# shift_register_MOSFET.net
KiCad netlist of a schematic drawn in EAGLE
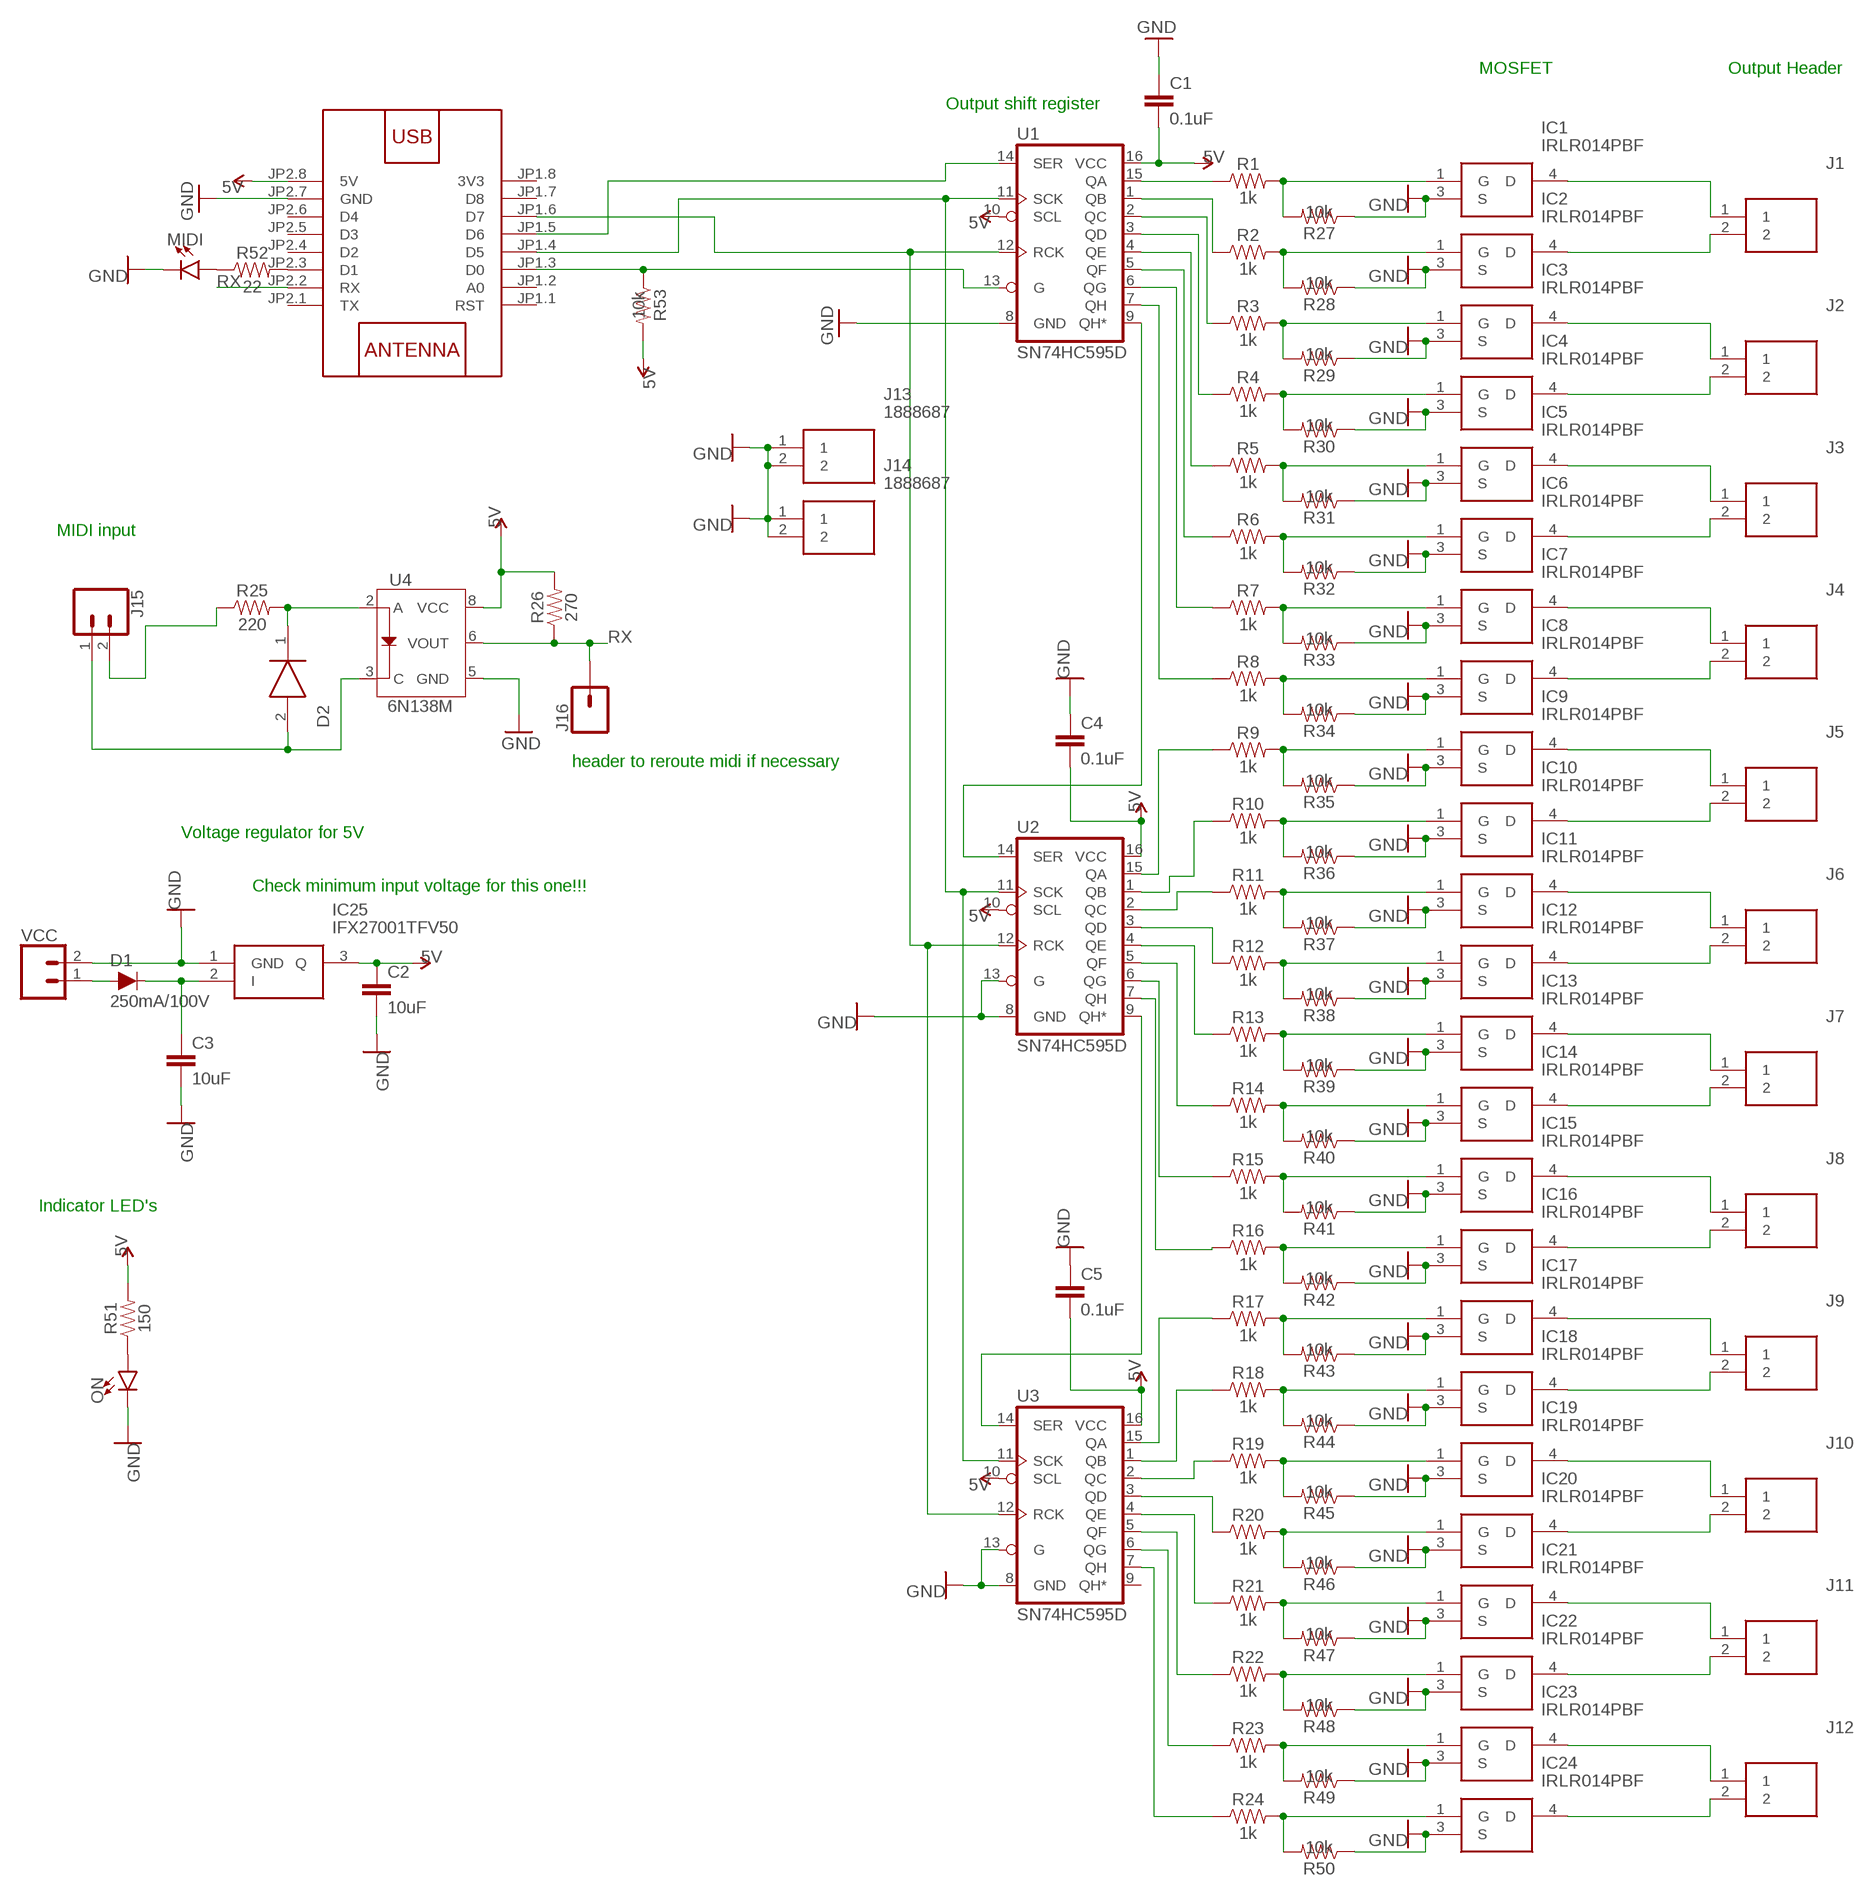
[diagram p0: schematic, sheet 1]

(export (version "E")
  (design (tool "Eeschema 10.0.6"))
  (components
    (comp (ref "C1")
      (value "0.1uF")
      (footprint "eagle-import:C0805")
      (libsource (lib "eagle-import") (part "C-EUC0805"))
    )
    (comp (ref "C2")
      (value "10uF")
      (footprint "eagle-import:C0805")
      (libsource (lib "eagle-import") (part "C-EUC0805"))
    )
    (comp (ref "C3")
      (value "10uF")
      (footprint "eagle-import:C0805")
      (libsource (lib "eagle-import") (part "C-EUC0805"))
    )
    (comp (ref "C4")
      (value "0.1uF")
      (footprint "eagle-import:C0805")
      (libsource (lib "eagle-import") (part "C-EUC0805"))
    )
    (comp (ref "C5")
      (value "0.1uF")
      (footprint "eagle-import:C0805")
      (libsource (lib "eagle-import") (part "C-EUC0805"))
    )
    (comp (ref "D1")
      (value "250mA/100V")
      (footprint "eagle-import:SOD-323")
      (libsource (lib "eagle-import") (part "DIODE-BAS16J"))
    )
    (comp (ref "D2")
      (value "1N914BWS")
      (footprint "eagle-import:SODFL2513X90N")
      (fields (field (name "MOUSER_PART_NUMBER") "512-1N914BWS") (field (name "RS_PART_NUMBER") "8051021P"))
      (libsource (lib "eagle-import") (part "1N914BWS"))
    )
    (comp (ref "IC1")
      (value "IRLR014PBF")
      (footprint "eagle-import:TO228P990X238-3N")
      (fields (field (name "MOUSER_PART_NUMBER") "844-IRLR014PBF") (field (name "RS_PART_NUMBER") "1780908"))
      (libsource (lib "eagle-import") (part "IRLR014PBF"))
    )
    (comp (ref "IC2")
      (value "IRLR014PBF")
      (footprint "eagle-import:TO228P990X238-3N")
      (fields (field (name "MOUSER_PART_NUMBER") "844-IRLR014PBF") (field (name "RS_PART_NUMBER") "1780908"))
      (libsource (lib "eagle-import") (part "IRLR014PBF"))
    )
    (comp (ref "IC3")
      (value "IRLR014PBF")
      (footprint "eagle-import:TO228P990X238-3N")
      (fields (field (name "MOUSER_PART_NUMBER") "844-IRLR014PBF") (field (name "RS_PART_NUMBER") "1780908"))
      (libsource (lib "eagle-import") (part "IRLR014PBF"))
    )
    (comp (ref "IC4")
      (value "IRLR014PBF")
      (footprint "eagle-import:TO228P990X238-3N")
      (fields (field (name "MOUSER_PART_NUMBER") "844-IRLR014PBF") (field (name "RS_PART_NUMBER") "1780908"))
      (libsource (lib "eagle-import") (part "IRLR014PBF"))
    )
    (comp (ref "IC5")
      (value "IRLR014PBF")
      (footprint "eagle-import:TO228P990X238-3N")
      (fields (field (name "MOUSER_PART_NUMBER") "844-IRLR014PBF") (field (name "RS_PART_NUMBER") "1780908"))
      (libsource (lib "eagle-import") (part "IRLR014PBF"))
    )
    (comp (ref "IC6")
      (value "IRLR014PBF")
      (footprint "eagle-import:TO228P990X238-3N")
      (fields (field (name "MOUSER_PART_NUMBER") "844-IRLR014PBF") (field (name "RS_PART_NUMBER") "1780908"))
      (libsource (lib "eagle-import") (part "IRLR014PBF"))
    )
    (comp (ref "IC7")
      (value "IRLR014PBF")
      (footprint "eagle-import:TO228P990X238-3N")
      (fields (field (name "MOUSER_PART_NUMBER") "844-IRLR014PBF") (field (name "RS_PART_NUMBER") "1780908"))
      (libsource (lib "eagle-import") (part "IRLR014PBF"))
    )
    (comp (ref "IC8")
      (value "IRLR014PBF")
      (footprint "eagle-import:TO228P990X238-3N")
      (fields (field (name "MOUSER_PART_NUMBER") "844-IRLR014PBF") (field (name "RS_PART_NUMBER") "1780908"))
      (libsource (lib "eagle-import") (part "IRLR014PBF"))
    )
    (comp (ref "IC9")
      (value "IRLR014PBF")
      (footprint "eagle-import:TO228P990X238-3N")
      (fields (field (name "MOUSER_PART_NUMBER") "844-IRLR014PBF") (field (name "RS_PART_NUMBER") "1780908"))
      (libsource (lib "eagle-import") (part "IRLR014PBF"))
    )
    (comp (ref "IC10")
      (value "IRLR014PBF")
      (footprint "eagle-import:TO228P990X238-3N")
      (fields (field (name "MOUSER_PART_NUMBER") "844-IRLR014PBF") (field (name "RS_PART_NUMBER") "1780908"))
      (libsource (lib "eagle-import") (part "IRLR014PBF"))
    )
    (comp (ref "IC11")
      (value "IRLR014PBF")
      (footprint "eagle-import:TO228P990X238-3N")
      (fields (field (name "MOUSER_PART_NUMBER") "844-IRLR014PBF") (field (name "RS_PART_NUMBER") "1780908"))
      (libsource (lib "eagle-import") (part "IRLR014PBF"))
    )
    (comp (ref "IC12")
      (value "IRLR014PBF")
      (footprint "eagle-import:TO228P990X238-3N")
      (fields (field (name "MOUSER_PART_NUMBER") "844-IRLR014PBF") (field (name "RS_PART_NUMBER") "1780908"))
      (libsource (lib "eagle-import") (part "IRLR014PBF"))
    )
    (comp (ref "IC13")
      (value "IRLR014PBF")
      (footprint "eagle-import:TO228P990X238-3N")
      (fields (field (name "MOUSER_PART_NUMBER") "844-IRLR014PBF") (field (name "RS_PART_NUMBER") "1780908"))
      (libsource (lib "eagle-import") (part "IRLR014PBF"))
    )
    (comp (ref "IC14")
      (value "IRLR014PBF")
      (footprint "eagle-import:TO228P990X238-3N")
      (fields (field (name "MOUSER_PART_NUMBER") "844-IRLR014PBF") (field (name "RS_PART_NUMBER") "1780908"))
      (libsource (lib "eagle-import") (part "IRLR014PBF"))
    )
    (comp (ref "IC15")
      (value "IRLR014PBF")
      (footprint "eagle-import:TO228P990X238-3N")
      (fields (field (name "MOUSER_PART_NUMBER") "844-IRLR014PBF") (field (name "RS_PART_NUMBER") "1780908"))
      (libsource (lib "eagle-import") (part "IRLR014PBF"))
    )
    (comp (ref "IC16")
      (value "IRLR014PBF")
      (footprint "eagle-import:TO228P990X238-3N")
      (fields (field (name "MOUSER_PART_NUMBER") "844-IRLR014PBF") (field (name "RS_PART_NUMBER") "1780908"))
      (libsource (lib "eagle-import") (part "IRLR014PBF"))
    )
    (comp (ref "IC17")
      (value "IRLR014PBF")
      (footprint "eagle-import:TO228P990X238-3N")
      (fields (field (name "MOUSER_PART_NUMBER") "844-IRLR014PBF") (field (name "RS_PART_NUMBER") "1780908"))
      (libsource (lib "eagle-import") (part "IRLR014PBF"))
    )
    (comp (ref "IC18")
      (value "IRLR014PBF")
      (footprint "eagle-import:TO228P990X238-3N")
      (fields (field (name "MOUSER_PART_NUMBER") "844-IRLR014PBF") (field (name "RS_PART_NUMBER") "1780908"))
      (libsource (lib "eagle-import") (part "IRLR014PBF"))
    )
    (comp (ref "IC19")
      (value "IRLR014PBF")
      (footprint "eagle-import:TO228P990X238-3N")
      (fields (field (name "MOUSER_PART_NUMBER") "844-IRLR014PBF") (field (name "RS_PART_NUMBER") "1780908"))
      (libsource (lib "eagle-import") (part "IRLR014PBF"))
    )
    (comp (ref "IC20")
      (value "IRLR014PBF")
      (footprint "eagle-import:TO228P990X238-3N")
      (fields (field (name "MOUSER_PART_NUMBER") "844-IRLR014PBF") (field (name "RS_PART_NUMBER") "1780908"))
      (libsource (lib "eagle-import") (part "IRLR014PBF"))
    )
    (comp (ref "IC21")
      (value "IRLR014PBF")
      (footprint "eagle-import:TO228P990X238-3N")
      (fields (field (name "MOUSER_PART_NUMBER") "844-IRLR014PBF") (field (name "RS_PART_NUMBER") "1780908"))
      (libsource (lib "eagle-import") (part "IRLR014PBF"))
    )
    (comp (ref "IC22")
      (value "IRLR014PBF")
      (footprint "eagle-import:TO228P990X238-3N")
      (fields (field (name "MOUSER_PART_NUMBER") "844-IRLR014PBF") (field (name "RS_PART_NUMBER") "1780908"))
      (libsource (lib "eagle-import") (part "IRLR014PBF"))
    )
    (comp (ref "IC23")
      (value "IRLR014PBF")
      (footprint "eagle-import:TO228P990X238-3N")
      (fields (field (name "MOUSER_PART_NUMBER") "844-IRLR014PBF") (field (name "RS_PART_NUMBER") "1780908"))
      (libsource (lib "eagle-import") (part "IRLR014PBF"))
    )
    (comp (ref "IC24")
      (value "IRLR014PBF")
      (footprint "eagle-import:TO228P990X238-3N")
      (fields (field (name "MOUSER_PART_NUMBER") "844-IRLR014PBF") (field (name "RS_PART_NUMBER") "1780908"))
      (libsource (lib "eagle-import") (part "IRLR014PBF"))
    )
    (comp (ref "IC25")
      (value "IFX27001TFV50")
      (footprint "eagle-import:PG-TO252-3-11")
      (fields (field (name "RS_PART_NUMBER") "1459664"))
      (libsource (lib "eagle-import") (part "IFX27001TFV50"))
    )
    (comp (ref "J1")
      (value "1888687")
      (footprint "eagle-import:SHDR2W90P0X508_1X2_1016X950X15")
      (fields (field (name "MOUSER_PART_NUMBER") "651-1888687") (field (name "RS_PART_NUMBER") "2509972333"))
      (libsource (lib "eagle-import") (part "1888687"))
    )
    (comp (ref "J2")
      (value "1888687")
      (footprint "eagle-import:SHDR2W90P0X508_1X2_1016X950X15")
      (fields (field (name "MOUSER_PART_NUMBER") "651-1888687") (field (name "RS_PART_NUMBER") "2509972333"))
      (libsource (lib "eagle-import") (part "1888687"))
    )
    (comp (ref "J3")
      (value "1888687")
      (footprint "eagle-import:SHDR2W90P0X508_1X2_1016X950X15")
      (fields (field (name "MOUSER_PART_NUMBER") "651-1888687") (field (name "RS_PART_NUMBER") "2509972333"))
      (libsource (lib "eagle-import") (part "1888687"))
    )
    (comp (ref "J4")
      (value "1888687")
      (footprint "eagle-import:SHDR2W90P0X508_1X2_1016X950X15")
      (fields (field (name "MOUSER_PART_NUMBER") "651-1888687") (field (name "RS_PART_NUMBER") "2509972333"))
      (libsource (lib "eagle-import") (part "1888687"))
    )
    (comp (ref "J5")
      (value "1888687")
      (footprint "eagle-import:SHDR2W90P0X508_1X2_1016X950X15")
      (fields (field (name "MOUSER_PART_NUMBER") "651-1888687") (field (name "RS_PART_NUMBER") "2509972333"))
      (libsource (lib "eagle-import") (part "1888687"))
    )
    (comp (ref "J6")
      (value "1888687")
      (footprint "eagle-import:SHDR2W90P0X508_1X2_1016X950X15")
      (fields (field (name "MOUSER_PART_NUMBER") "651-1888687") (field (name "RS_PART_NUMBER") "2509972333"))
      (libsource (lib "eagle-import") (part "1888687"))
    )
    (comp (ref "J7")
      (value "1888687")
      (footprint "eagle-import:SHDR2W90P0X508_1X2_1016X950X15")
      (fields (field (name "MOUSER_PART_NUMBER") "651-1888687") (field (name "RS_PART_NUMBER") "2509972333"))
      (libsource (lib "eagle-import") (part "1888687"))
    )
    (comp (ref "J8")
      (value "1888687")
      (footprint "eagle-import:SHDR2W90P0X508_1X2_1016X950X15")
      (fields (field (name "MOUSER_PART_NUMBER") "651-1888687") (field (name "RS_PART_NUMBER") "2509972333"))
      (libsource (lib "eagle-import") (part "1888687"))
    )
    (comp (ref "J9")
      (value "1888687")
      (footprint "eagle-import:SHDR2W90P0X508_1X2_1016X950X15")
      (fields (field (name "MOUSER_PART_NUMBER") "651-1888687") (field (name "RS_PART_NUMBER") "2509972333"))
      (libsource (lib "eagle-import") (part "1888687"))
    )
    (comp (ref "J10")
      (value "1888687")
      (footprint "eagle-import:SHDR2W90P0X508_1X2_1016X950X15")
      (fields (field (name "MOUSER_PART_NUMBER") "651-1888687") (field (name "RS_PART_NUMBER") "2509972333"))
      (libsource (lib "eagle-import") (part "1888687"))
    )
    (comp (ref "J11")
      (value "1888687")
      (footprint "eagle-import:SHDR2W90P0X508_1X2_1016X950X15")
      (fields (field (name "MOUSER_PART_NUMBER") "651-1888687") (field (name "RS_PART_NUMBER") "2509972333"))
      (libsource (lib "eagle-import") (part "1888687"))
    )
    (comp (ref "J12")
      (value "1888687")
      (footprint "eagle-import:SHDR2W90P0X508_1X2_1016X950X15")
      (fields (field (name "MOUSER_PART_NUMBER") "651-1888687") (field (name "RS_PART_NUMBER") "2509972333"))
      (libsource (lib "eagle-import") (part "1888687"))
    )
    (comp (ref "J13")
      (value "1888687")
      (footprint "eagle-import:SHDR2W90P0X508_1X2_1016X950X15")
      (fields (field (name "MOUSER_PART_NUMBER") "651-1888687") (field (name "RS_PART_NUMBER") "2509972333"))
      (libsource (lib "eagle-import") (part "1888687"))
    )
    (comp (ref "J14")
      (value "1888687")
      (footprint "eagle-import:SHDR2W90P0X508_1X2_1016X950X15")
      (fields (field (name "MOUSER_PART_NUMBER") "651-1888687") (field (name "RS_PART_NUMBER") "2509972333"))
      (libsource (lib "eagle-import") (part "1888687"))
    )
    (comp (ref "J15")
      (value "CONN_02")
      (footprint "eagle-import:1X02")
      (libsource (lib "eagle-import") (part "CONN_02"))
    )
    (comp (ref "J16")
      (value "CONN_01")
      (footprint "eagle-import:1X01")
      (libsource (lib "eagle-import") (part "CONN_01"))
    )
    (comp (ref "MIDI")
      (value "LED3MM")
      (footprint "eagle-import:LED_3MM")
      (libsource (lib "eagle-import") (part "LED3MM"))
    )
    (comp (ref "ON")
      (value "LED3MM")
      (footprint "eagle-import:LED_3MM")
      (libsource (lib "eagle-import") (part "LED3MM"))
    )
    (comp (ref "R1")
      (value "1k")
      (footprint "eagle-import:0805")
      (libsource (lib "eagle-import") (part "RESISTOR0805"))
    )
    (comp (ref "R2")
      (value "1k")
      (footprint "eagle-import:0805")
      (libsource (lib "eagle-import") (part "RESISTOR0805"))
    )
    (comp (ref "R3")
      (value "1k")
      (footprint "eagle-import:0805")
      (libsource (lib "eagle-import") (part "RESISTOR0805"))
    )
    (comp (ref "R4")
      (value "1k")
      (footprint "eagle-import:0805")
      (libsource (lib "eagle-import") (part "RESISTOR0805"))
    )
    (comp (ref "R5")
      (value "1k")
      (footprint "eagle-import:0805")
      (libsource (lib "eagle-import") (part "RESISTOR0805"))
    )
    (comp (ref "R6")
      (value "1k")
      (footprint "eagle-import:0805")
      (libsource (lib "eagle-import") (part "RESISTOR0805"))
    )
    (comp (ref "R7")
      (value "1k")
      (footprint "eagle-import:0805")
      (libsource (lib "eagle-import") (part "RESISTOR0805"))
    )
    (comp (ref "R8")
      (value "1k")
      (footprint "eagle-import:0805")
      (libsource (lib "eagle-import") (part "RESISTOR0805"))
    )
    (comp (ref "R9")
      (value "1k")
      (footprint "eagle-import:0805")
      (libsource (lib "eagle-import") (part "RESISTOR0805"))
    )
    (comp (ref "R10")
      (value "1k")
      (footprint "eagle-import:0805")
      (libsource (lib "eagle-import") (part "RESISTOR0805"))
    )
    (comp (ref "R11")
      (value "1k")
      (footprint "eagle-import:0805")
      (libsource (lib "eagle-import") (part "RESISTOR0805"))
    )
    (comp (ref "R12")
      (value "1k")
      (footprint "eagle-import:0805")
      (libsource (lib "eagle-import") (part "RESISTOR0805"))
    )
    (comp (ref "R13")
      (value "1k")
      (footprint "eagle-import:0805")
      (libsource (lib "eagle-import") (part "RESISTOR0805"))
    )
    (comp (ref "R14")
      (value "1k")
      (footprint "eagle-import:0805")
      (libsource (lib "eagle-import") (part "RESISTOR0805"))
    )
    (comp (ref "R15")
      (value "1k")
      (footprint "eagle-import:0805")
      (libsource (lib "eagle-import") (part "RESISTOR0805"))
    )
    (comp (ref "R16")
      (value "1k")
      (footprint "eagle-import:0805")
      (libsource (lib "eagle-import") (part "RESISTOR0805"))
    )
    (comp (ref "R17")
      (value "1k")
      (footprint "eagle-import:0805")
      (libsource (lib "eagle-import") (part "RESISTOR0805"))
    )
    (comp (ref "R18")
      (value "1k")
      (footprint "eagle-import:0805")
      (libsource (lib "eagle-import") (part "RESISTOR0805"))
    )
    (comp (ref "R19")
      (value "1k")
      (footprint "eagle-import:0805")
      (libsource (lib "eagle-import") (part "RESISTOR0805"))
    )
    (comp (ref "R20")
      (value "1k")
      (footprint "eagle-import:0805")
      (libsource (lib "eagle-import") (part "RESISTOR0805"))
    )
    (comp (ref "R21")
      (value "1k")
      (footprint "eagle-import:0805")
      (libsource (lib "eagle-import") (part "RESISTOR0805"))
    )
    (comp (ref "R22")
      (value "1k")
      (footprint "eagle-import:0805")
      (libsource (lib "eagle-import") (part "RESISTOR0805"))
    )
    (comp (ref "R23")
      (value "1k")
      (footprint "eagle-import:0805")
      (libsource (lib "eagle-import") (part "RESISTOR0805"))
    )
    (comp (ref "R24")
      (value "1k")
      (footprint "eagle-import:0805")
      (libsource (lib "eagle-import") (part "RESISTOR0805"))
    )
    (comp (ref "R25")
      (value "220")
      (footprint "eagle-import:0805")
      (libsource (lib "eagle-import") (part "RESISTOR0805"))
    )
    (comp (ref "R26")
      (value "270")
      (footprint "eagle-import:0805")
      (libsource (lib "eagle-import") (part "RESISTOR0805"))
    )
    (comp (ref "R27")
      (value "10k")
      (footprint "eagle-import:0805")
      (libsource (lib "eagle-import") (part "RESISTOR0805"))
    )
    (comp (ref "R28")
      (value "10k")
      (footprint "eagle-import:0805")
      (libsource (lib "eagle-import") (part "RESISTOR0805"))
    )
    (comp (ref "R29")
      (value "10k")
      (footprint "eagle-import:0805")
      (libsource (lib "eagle-import") (part "RESISTOR0805"))
    )
    (comp (ref "R30")
      (value "10k")
      (footprint "eagle-import:0805")
      (libsource (lib "eagle-import") (part "RESISTOR0805"))
    )
    (comp (ref "R31")
      (value "10k")
      (footprint "eagle-import:0805")
      (libsource (lib "eagle-import") (part "RESISTOR0805"))
    )
    (comp (ref "R32")
      (value "10k")
      (footprint "eagle-import:0805")
      (libsource (lib "eagle-import") (part "RESISTOR0805"))
    )
    (comp (ref "R33")
      (value "10k")
      (footprint "eagle-import:0805")
      (libsource (lib "eagle-import") (part "RESISTOR0805"))
    )
    (comp (ref "R34")
      (value "10k")
      (footprint "eagle-import:0805")
      (libsource (lib "eagle-import") (part "RESISTOR0805"))
    )
    (comp (ref "R35")
      (value "10k")
      (footprint "eagle-import:0805")
      (libsource (lib "eagle-import") (part "RESISTOR0805"))
    )
    (comp (ref "R36")
      (value "10k")
      (footprint "eagle-import:0805")
      (libsource (lib "eagle-import") (part "RESISTOR0805"))
    )
    (comp (ref "R37")
      (value "10k")
      (footprint "eagle-import:0805")
      (libsource (lib "eagle-import") (part "RESISTOR0805"))
    )
    (comp (ref "R38")
      (value "10k")
      (footprint "eagle-import:0805")
      (libsource (lib "eagle-import") (part "RESISTOR0805"))
    )
    (comp (ref "R39")
      (value "10k")
      (footprint "eagle-import:0805")
      (libsource (lib "eagle-import") (part "RESISTOR0805"))
    )
    (comp (ref "R40")
      (value "10k")
      (footprint "eagle-import:0805")
      (libsource (lib "eagle-import") (part "RESISTOR0805"))
    )
    (comp (ref "R41")
      (value "10k")
      (footprint "eagle-import:0805")
      (libsource (lib "eagle-import") (part "RESISTOR0805"))
    )
    (comp (ref "R42")
      (value "10k")
      (footprint "eagle-import:0805")
      (libsource (lib "eagle-import") (part "RESISTOR0805"))
    )
    (comp (ref "R43")
      (value "10k")
      (footprint "eagle-import:0805")
      (libsource (lib "eagle-import") (part "RESISTOR0805"))
    )
    (comp (ref "R44")
      (value "10k")
      (footprint "eagle-import:0805")
      (libsource (lib "eagle-import") (part "RESISTOR0805"))
    )
    (comp (ref "R45")
      (value "10k")
      (footprint "eagle-import:0805")
      (libsource (lib "eagle-import") (part "RESISTOR0805"))
    )
    (comp (ref "R46")
      (value "10k")
      (footprint "eagle-import:0805")
      (libsource (lib "eagle-import") (part "RESISTOR0805"))
    )
    (comp (ref "R47")
      (value "10k")
      (footprint "eagle-import:0805")
      (libsource (lib "eagle-import") (part "RESISTOR0805"))
    )
    (comp (ref "R48")
      (value "10k")
      (footprint "eagle-import:0805")
      (libsource (lib "eagle-import") (part "RESISTOR0805"))
    )
    (comp (ref "R49")
      (value "10k")
      (footprint "eagle-import:0805")
      (libsource (lib "eagle-import") (part "RESISTOR0805"))
    )
    (comp (ref "R50")
      (value "10k")
      (footprint "eagle-import:0805")
      (libsource (lib "eagle-import") (part "RESISTOR0805"))
    )
    (comp (ref "R51")
      (value "150")
      (footprint "eagle-import:0805")
      (libsource (lib "eagle-import") (part "RESISTOR0805"))
    )
    (comp (ref "R52")
      (value "22")
      (footprint "eagle-import:0805")
      (libsource (lib "eagle-import") (part "RESISTOR0805"))
    )
    (comp (ref "R53")
      (value "10k")
      (footprint "eagle-import:0805")
      (libsource (lib "eagle-import") (part "RESISTOR0805"))
    )
    (comp (ref "U$1")
      (value "WEMOS-D1-MINI")
      (footprint "eagle-import:WEMOS-D1-MINI")
      (libsource (lib "eagle-import") (part "WEMOS-D1-MINI"))
    )
    (comp (ref "U1")
      (value "SN74HC595D")
      (footprint "eagle-import:SO16")
      (libsource (lib "eagle-import") (part "74595DHC"))
    )
    (comp (ref "U2")
      (value "SN74HC595D")
      (footprint "eagle-import:SO16")
      (libsource (lib "eagle-import") (part "74595DHC"))
    )
    (comp (ref "U3")
      (value "SN74HC595D")
      (footprint "eagle-import:SO16")
      (libsource (lib "eagle-import") (part "74595DHC"))
    )
    (comp (ref "U4")
      (value "6N138M")
      (footprint "eagle-import:8-SMD")
      (libsource (lib "eagle-import") (part "OPTO_DARL_6N138S"))
    )
    (comp (ref "VCC")
      (value "CONN_02")
      (footprint "eagle-import:1X02")
      (libsource (lib "eagle-import") (part "CONN_02"))
    )
  )
  (nets
    (net (code "1") (name "/3V3") (class "Default")
      (node (ref "U$1") (pin "JP1.8") (pinfunction "3V3_JP1.8") (pintype "power_in"))
    )
    (net (code "2") (name "/RX") (class "Default")
      (node (ref "J16") (pin "1") (pinfunction "1_1") (pintype "passive"))
      (node (ref "R26") (pin "1") (pinfunction "1_1") (pintype "passive"))
      (node (ref "U$1") (pin "JP2.2") (pinfunction "RX_JP2.2") (pintype "bidirectional"))
      (node (ref "U4") (pin "6") (pinfunction "VOUT_6") (pintype "bidirectional"))
    )
    (net (code "3") (name "5V") (class "Default")
      (node (ref "C1") (pin "2") (pinfunction "2_2") (pintype "passive"))
      (node (ref "C2") (pin "1") (pinfunction "1_1") (pintype "passive"))
      (node (ref "C4") (pin "2") (pinfunction "2_2") (pintype "passive"))
      (node (ref "C5") (pin "2") (pinfunction "2_2") (pintype "passive"))
      (node (ref "IC25") (pin "3") (pinfunction "Q_3") (pintype "bidirectional"))
      (node (ref "R26") (pin "2") (pinfunction "2_2") (pintype "passive"))
      (node (ref "R51") (pin "2") (pinfunction "2_2") (pintype "passive"))
      (node (ref "R53") (pin "2") (pinfunction "2_2") (pintype "passive"))
      (node (ref "U$1") (pin "JP2.8") (pinfunction "5V_JP2.8") (pintype "power_in"))
      (node (ref "U1") (pin "10") (pinfunction "SCL_10") (pintype "input"))
      (node (ref "U1") (pin "16") (pinfunction "VCC_16") (pintype "power_in"))
      (node (ref "U2") (pin "10") (pinfunction "SCL_10") (pintype "input"))
      (node (ref "U2") (pin "16") (pinfunction "VCC_16") (pintype "power_in"))
      (node (ref "U3") (pin "10") (pinfunction "SCL_10") (pintype "input"))
      (node (ref "U3") (pin "16") (pinfunction "VCC_16") (pintype "power_in"))
      (node (ref "U4") (pin "8") (pinfunction "VCC_8") (pintype "bidirectional"))
    )
    (net (code "4") (name "GND") (class "Default")
      (node (ref "C1") (pin "1") (pinfunction "1_1") (pintype "passive"))
      (node (ref "C2") (pin "2") (pinfunction "2_2") (pintype "passive"))
      (node (ref "C3") (pin "2") (pinfunction "2_2") (pintype "passive"))
      (node (ref "C4") (pin "1") (pinfunction "1_1") (pintype "passive"))
      (node (ref "C5") (pin "1") (pinfunction "1_1") (pintype "passive"))
      (node (ref "IC1") (pin "3") (pinfunction "S_3") (pintype "bidirectional"))
      (node (ref "IC10") (pin "3") (pinfunction "S_3") (pintype "bidirectional"))
      (node (ref "IC11") (pin "3") (pinfunction "S_3") (pintype "bidirectional"))
      (node (ref "IC12") (pin "3") (pinfunction "S_3") (pintype "bidirectional"))
      (node (ref "IC13") (pin "3") (pinfunction "S_3") (pintype "bidirectional"))
      (node (ref "IC14") (pin "3") (pinfunction "S_3") (pintype "bidirectional"))
      (node (ref "IC15") (pin "3") (pinfunction "S_3") (pintype "bidirectional"))
      (node (ref "IC16") (pin "3") (pinfunction "S_3") (pintype "bidirectional"))
      (node (ref "IC17") (pin "3") (pinfunction "S_3") (pintype "bidirectional"))
      (node (ref "IC18") (pin "3") (pinfunction "S_3") (pintype "bidirectional"))
      (node (ref "IC19") (pin "3") (pinfunction "S_3") (pintype "bidirectional"))
      (node (ref "IC2") (pin "3") (pinfunction "S_3") (pintype "bidirectional"))
      (node (ref "IC20") (pin "3") (pinfunction "S_3") (pintype "bidirectional"))
      (node (ref "IC21") (pin "3") (pinfunction "S_3") (pintype "bidirectional"))
      (node (ref "IC22") (pin "3") (pinfunction "S_3") (pintype "bidirectional"))
      (node (ref "IC23") (pin "3") (pinfunction "S_3") (pintype "bidirectional"))
      (node (ref "IC24") (pin "3") (pinfunction "S_3") (pintype "bidirectional"))
      (node (ref "IC25") (pin "1") (pinfunction "GND_1") (pintype "bidirectional"))
      (node (ref "IC3") (pin "3") (pinfunction "S_3") (pintype "bidirectional"))
      (node (ref "IC4") (pin "3") (pinfunction "S_3") (pintype "bidirectional"))
      (node (ref "IC5") (pin "3") (pinfunction "S_3") (pintype "bidirectional"))
      (node (ref "IC6") (pin "3") (pinfunction "S_3") (pintype "bidirectional"))
      (node (ref "IC7") (pin "3") (pinfunction "S_3") (pintype "bidirectional"))
      (node (ref "IC8") (pin "3") (pinfunction "S_3") (pintype "bidirectional"))
      (node (ref "IC9") (pin "3") (pinfunction "S_3") (pintype "bidirectional"))
      (node (ref "J13") (pin "1") (pinfunction "1_1") (pintype "bidirectional"))
      (node (ref "J13") (pin "2") (pinfunction "2_2") (pintype "bidirectional"))
      (node (ref "J14") (pin "1") (pinfunction "1_1") (pintype "bidirectional"))
      (node (ref "J14") (pin "2") (pinfunction "2_2") (pintype "bidirectional"))
      (node (ref "MIDI") (pin "K") (pinfunction "C_K") (pintype "passive"))
      (node (ref "ON") (pin "K") (pinfunction "C_K") (pintype "passive"))
      (node (ref "R27") (pin "1") (pinfunction "1_1") (pintype "passive"))
      (node (ref "R28") (pin "1") (pinfunction "1_1") (pintype "passive"))
      (node (ref "R29") (pin "1") (pinfunction "1_1") (pintype "passive"))
      (node (ref "R30") (pin "1") (pinfunction "1_1") (pintype "passive"))
      (node (ref "R31") (pin "1") (pinfunction "1_1") (pintype "passive"))
      (node (ref "R32") (pin "1") (pinfunction "1_1") (pintype "passive"))
      (node (ref "R33") (pin "1") (pinfunction "1_1") (pintype "passive"))
      (node (ref "R34") (pin "1") (pinfunction "1_1") (pintype "passive"))
      (node (ref "R35") (pin "1") (pinfunction "1_1") (pintype "passive"))
      (node (ref "R36") (pin "1") (pinfunction "1_1") (pintype "passive"))
      (node (ref "R37") (pin "1") (pinfunction "1_1") (pintype "passive"))
      (node (ref "R38") (pin "1") (pinfunction "1_1") (pintype "passive"))
      (node (ref "R39") (pin "1") (pinfunction "1_1") (pintype "passive"))
      (node (ref "R40") (pin "1") (pinfunction "1_1") (pintype "passive"))
      (node (ref "R41") (pin "1") (pinfunction "1_1") (pintype "passive"))
      (node (ref "R42") (pin "1") (pinfunction "1_1") (pintype "passive"))
      (node (ref "R43") (pin "1") (pinfunction "1_1") (pintype "passive"))
      (node (ref "R44") (pin "1") (pinfunction "1_1") (pintype "passive"))
      (node (ref "R45") (pin "1") (pinfunction "1_1") (pintype "passive"))
      (node (ref "R46") (pin "1") (pinfunction "1_1") (pintype "passive"))
      (node (ref "R47") (pin "1") (pinfunction "1_1") (pintype "passive"))
      (node (ref "R48") (pin "1") (pinfunction "1_1") (pintype "passive"))
      (node (ref "R49") (pin "1") (pinfunction "1_1") (pintype "passive"))
      (node (ref "R50") (pin "1") (pinfunction "1_1") (pintype "passive"))
      (node (ref "U$1") (pin "JP2.7") (pinfunction "GND_JP2.7") (pintype "power_in"))
      (node (ref "U1") (pin "8") (pinfunction "GND_8") (pintype "power_in"))
      (node (ref "U2") (pin "13") (pinfunction "G_13") (pintype "input"))
      (node (ref "U2") (pin "8") (pinfunction "GND_8") (pintype "power_in"))
      (node (ref "U3") (pin "13") (pinfunction "G_13") (pintype "input"))
      (node (ref "U3") (pin "8") (pinfunction "GND_8") (pintype "power_in"))
      (node (ref "U4") (pin "5") (pinfunction "GND_5") (pintype "bidirectional"))
      (node (ref "VCC") (pin "2") (pinfunction "2_2") (pintype "passive"))
    )
    (net (code "5") (name "Net-(D1-PadA)") (class "Default")
      (node (ref "D1") (pin "A") (pinfunction "A_A") (pintype "passive"))
      (node (ref "VCC") (pin "1") (pinfunction "1_1") (pintype "passive"))
    )
    (net (code "6") (name "Net-(D2-A)") (class "Default")
      (node (ref "D2") (pin "2") (pinfunction "A_2") (pintype "bidirectional"))
      (node (ref "J15") (pin "1") (pinfunction "1_1") (pintype "passive"))
      (node (ref "U4") (pin "3") (pinfunction "C_3") (pintype "bidirectional"))
    )
    (net (code "7") (name "Net-(D2-K)") (class "Default")
      (node (ref "D2") (pin "1") (pinfunction "K_1") (pintype "bidirectional"))
      (node (ref "R25") (pin "2") (pinfunction "2_2") (pintype "passive"))
      (node (ref "U4") (pin "2") (pinfunction "A_2") (pintype "bidirectional"))
    )
    (net (code "8") (name "Net-(IC1-D)") (class "Default")
      (node (ref "IC1") (pin "4") (pinfunction "D_4") (pintype "bidirectional"))
      (node (ref "J1") (pin "1") (pinfunction "1_1") (pintype "bidirectional"))
    )
    (net (code "9") (name "Net-(IC1-G)") (class "Default")
      (node (ref "IC1") (pin "1") (pinfunction "G_1") (pintype "bidirectional"))
      (node (ref "R1") (pin "2") (pinfunction "2_2") (pintype "passive"))
      (node (ref "R27") (pin "2") (pinfunction "2_2") (pintype "passive"))
    )
    (net (code "10") (name "Net-(IC2-D)") (class "Default")
      (node (ref "IC2") (pin "4") (pinfunction "D_4") (pintype "bidirectional"))
      (node (ref "J1") (pin "2") (pinfunction "2_2") (pintype "bidirectional"))
    )
    (net (code "11") (name "Net-(IC2-G)") (class "Default")
      (node (ref "IC2") (pin "1") (pinfunction "G_1") (pintype "bidirectional"))
      (node (ref "R2") (pin "2") (pinfunction "2_2") (pintype "passive"))
      (node (ref "R28") (pin "2") (pinfunction "2_2") (pintype "passive"))
    )
    (net (code "12") (name "Net-(IC3-D)") (class "Default")
      (node (ref "IC3") (pin "4") (pinfunction "D_4") (pintype "bidirectional"))
      (node (ref "J2") (pin "1") (pinfunction "1_1") (pintype "bidirectional"))
    )
    (net (code "13") (name "Net-(IC3-G)") (class "Default")
      (node (ref "IC3") (pin "1") (pinfunction "G_1") (pintype "bidirectional"))
      (node (ref "R29") (pin "2") (pinfunction "2_2") (pintype "passive"))
      (node (ref "R3") (pin "2") (pinfunction "2_2") (pintype "passive"))
    )
    (net (code "14") (name "Net-(IC4-D)") (class "Default")
      (node (ref "IC4") (pin "4") (pinfunction "D_4") (pintype "bidirectional"))
      (node (ref "J2") (pin "2") (pinfunction "2_2") (pintype "bidirectional"))
    )
    (net (code "15") (name "Net-(IC4-G)") (class "Default")
      (node (ref "IC4") (pin "1") (pinfunction "G_1") (pintype "bidirectional"))
      (node (ref "R30") (pin "2") (pinfunction "2_2") (pintype "passive"))
      (node (ref "R4") (pin "2") (pinfunction "2_2") (pintype "passive"))
    )
    (net (code "16") (name "Net-(IC5-D)") (class "Default")
      (node (ref "IC5") (pin "4") (pinfunction "D_4") (pintype "bidirectional"))
      (node (ref "J3") (pin "1") (pinfunction "1_1") (pintype "bidirectional"))
    )
    (net (code "17") (name "Net-(IC5-G)") (class "Default")
      (node (ref "IC5") (pin "1") (pinfunction "G_1") (pintype "bidirectional"))
      (node (ref "R31") (pin "2") (pinfunction "2_2") (pintype "passive"))
      (node (ref "R5") (pin "2") (pinfunction "2_2") (pintype "passive"))
    )
    (net (code "18") (name "Net-(IC6-D)") (class "Default")
      (node (ref "IC6") (pin "4") (pinfunction "D_4") (pintype "bidirectional"))
      (node (ref "J3") (pin "2") (pinfunction "2_2") (pintype "bidirectional"))
    )
    (net (code "19") (name "Net-(IC6-G)") (class "Default")
      (node (ref "IC6") (pin "1") (pinfunction "G_1") (pintype "bidirectional"))
      (node (ref "R32") (pin "2") (pinfunction "2_2") (pintype "passive"))
      (node (ref "R6") (pin "2") (pinfunction "2_2") (pintype "passive"))
    )
    (net (code "20") (name "Net-(IC7-D)") (class "Default")
      (node (ref "IC7") (pin "4") (pinfunction "D_4") (pintype "bidirectional"))
      (node (ref "J4") (pin "1") (pinfunction "1_1") (pintype "bidirectional"))
    )
    (net (code "21") (name "Net-(IC7-G)") (class "Default")
      (node (ref "IC7") (pin "1") (pinfunction "G_1") (pintype "bidirectional"))
      (node (ref "R33") (pin "2") (pinfunction "2_2") (pintype "passive"))
      (node (ref "R7") (pin "2") (pinfunction "2_2") (pintype "passive"))
    )
    (net (code "22") (name "Net-(IC8-D)") (class "Default")
      (node (ref "IC8") (pin "4") (pinfunction "D_4") (pintype "bidirectional"))
      (node (ref "J4") (pin "2") (pinfunction "2_2") (pintype "bidirectional"))
    )
    (net (code "23") (name "Net-(IC8-G)") (class "Default")
      (node (ref "IC8") (pin "1") (pinfunction "G_1") (pintype "bidirectional"))
      (node (ref "R34") (pin "2") (pinfunction "2_2") (pintype "passive"))
      (node (ref "R8") (pin "2") (pinfunction "2_2") (pintype "passive"))
    )
    (net (code "24") (name "Net-(IC9-D)") (class "Default")
      (node (ref "IC9") (pin "4") (pinfunction "D_4") (pintype "bidirectional"))
      (node (ref "J5") (pin "1") (pinfunction "1_1") (pintype "bidirectional"))
    )
    (net (code "25") (name "Net-(IC9-G)") (class "Default")
      (node (ref "IC9") (pin "1") (pinfunction "G_1") (pintype "bidirectional"))
      (node (ref "R35") (pin "2") (pinfunction "2_2") (pintype "passive"))
      (node (ref "R9") (pin "2") (pinfunction "2_2") (pintype "passive"))
    )
    (net (code "26") (name "Net-(IC10-D)") (class "Default")
      (node (ref "IC10") (pin "4") (pinfunction "D_4") (pintype "bidirectional"))
      (node (ref "J5") (pin "2") (pinfunction "2_2") (pintype "bidirectional"))
    )
    (net (code "27") (name "Net-(IC10-G)") (class "Default")
      (node (ref "IC10") (pin "1") (pinfunction "G_1") (pintype "bidirectional"))
      (node (ref "R10") (pin "2") (pinfunction "2_2") (pintype "passive"))
      (node (ref "R36") (pin "2") (pinfunction "2_2") (pintype "passive"))
    )
    (net (code "28") (name "Net-(IC11-D)") (class "Default")
      (node (ref "IC11") (pin "4") (pinfunction "D_4") (pintype "bidirectional"))
      (node (ref "J6") (pin "1") (pinfunction "1_1") (pintype "bidirectional"))
    )
    (net (code "29") (name "Net-(IC11-G)") (class "Default")
      (node (ref "IC11") (pin "1") (pinfunction "G_1") (pintype "bidirectional"))
      (node (ref "R11") (pin "2") (pinfunction "2_2") (pintype "passive"))
      (node (ref "R37") (pin "2") (pinfunction "2_2") (pintype "passive"))
    )
    (net (code "30") (name "Net-(IC12-D)") (class "Default")
      (node (ref "IC12") (pin "4") (pinfunction "D_4") (pintype "bidirectional"))
      (node (ref "J6") (pin "2") (pinfunction "2_2") (pintype "bidirectional"))
    )
    (net (code "31") (name "Net-(IC12-G)") (class "Default")
      (node (ref "IC12") (pin "1") (pinfunction "G_1") (pintype "bidirectional"))
      (node (ref "R12") (pin "2") (pinfunction "2_2") (pintype "passive"))
      (node (ref "R38") (pin "2") (pinfunction "2_2") (pintype "passive"))
    )
    (net (code "32") (name "Net-(IC13-D)") (class "Default")
      (node (ref "IC13") (pin "4") (pinfunction "D_4") (pintype "bidirectional"))
      (node (ref "J7") (pin "1") (pinfunction "1_1") (pintype "bidirectional"))
    )
    (net (code "33") (name "Net-(IC13-G)") (class "Default")
      (node (ref "IC13") (pin "1") (pinfunction "G_1") (pintype "bidirectional"))
      (node (ref "R13") (pin "2") (pinfunction "2_2") (pintype "passive"))
      (node (ref "R39") (pin "2") (pinfunction "2_2") (pintype "passive"))
    )
    (net (code "34") (name "Net-(IC14-D)") (class "Default")
      (node (ref "IC14") (pin "4") (pinfunction "D_4") (pintype "bidirectional"))
      (node (ref "J7") (pin "2") (pinfunction "2_2") (pintype "bidirectional"))
    )
    (net (code "35") (name "Net-(IC14-G)") (class "Default")
      (node (ref "IC14") (pin "1") (pinfunction "G_1") (pintype "bidirectional"))
      (node (ref "R14") (pin "2") (pinfunction "2_2") (pintype "passive"))
      (node (ref "R40") (pin "2") (pinfunction "2_2") (pintype "passive"))
    )
    (net (code "36") (name "Net-(IC15-D)") (class "Default")
      (node (ref "IC15") (pin "4") (pinfunction "D_4") (pintype "bidirectional"))
      (node (ref "J8") (pin "1") (pinfunction "1_1") (pintype "bidirectional"))
    )
    (net (code "37") (name "Net-(IC15-G)") (class "Default")
      (node (ref "IC15") (pin "1") (pinfunction "G_1") (pintype "bidirectional"))
      (node (ref "R15") (pin "2") (pinfunction "2_2") (pintype "passive"))
      (node (ref "R41") (pin "2") (pinfunction "2_2") (pintype "passive"))
    )
    (net (code "38") (name "Net-(IC16-D)") (class "Default")
      (node (ref "IC16") (pin "4") (pinfunction "D_4") (pintype "bidirectional"))
      (node (ref "J8") (pin "2") (pinfunction "2_2") (pintype "bidirectional"))
    )
    (net (code "39") (name "Net-(IC16-G)") (class "Default")
      (node (ref "IC16") (pin "1") (pinfunction "G_1") (pintype "bidirectional"))
      (node (ref "R16") (pin "2") (pinfunction "2_2") (pintype "passive"))
      (node (ref "R42") (pin "2") (pinfunction "2_2") (pintype "passive"))
    )
    (net (code "40") (name "Net-(IC17-D)") (class "Default")
      (node (ref "IC17") (pin "4") (pinfunction "D_4") (pintype "bidirectional"))
      (node (ref "J9") (pin "1") (pinfunction "1_1") (pintype "bidirectional"))
    )
    (net (code "41") (name "Net-(IC17-G)") (class "Default")
      (node (ref "IC17") (pin "1") (pinfunction "G_1") (pintype "bidirectional"))
      (node (ref "R17") (pin "2") (pinfunction "2_2") (pintype "passive"))
      (node (ref "R43") (pin "2") (pinfunction "2_2") (pintype "passive"))
    )
    (net (code "42") (name "Net-(IC18-D)") (class "Default")
      (node (ref "IC18") (pin "4") (pinfunction "D_4") (pintype "bidirectional"))
      (node (ref "J9") (pin "2") (pinfunction "2_2") (pintype "bidirectional"))
    )
    (net (code "43") (name "Net-(IC18-G)") (class "Default")
      (node (ref "IC18") (pin "1") (pinfunction "G_1") (pintype "bidirectional"))
      (node (ref "R18") (pin "2") (pinfunction "2_2") (pintype "passive"))
      (node (ref "R44") (pin "2") (pinfunction "2_2") (pintype "passive"))
    )
    (net (code "44") (name "Net-(IC19-D)") (class "Default")
      (node (ref "IC19") (pin "4") (pinfunction "D_4") (pintype "bidirectional"))
      (node (ref "J10") (pin "1") (pinfunction "1_1") (pintype "bidirectional"))
    )
    (net (code "45") (name "Net-(IC19-G)") (class "Default")
      (node (ref "IC19") (pin "1") (pinfunction "G_1") (pintype "bidirectional"))
      (node (ref "R19") (pin "2") (pinfunction "2_2") (pintype "passive"))
      (node (ref "R45") (pin "2") (pinfunction "2_2") (pintype "passive"))
    )
    (net (code "46") (name "Net-(IC20-D)") (class "Default")
      (node (ref "IC20") (pin "4") (pinfunction "D_4") (pintype "bidirectional"))
      (node (ref "J10") (pin "2") (pinfunction "2_2") (pintype "bidirectional"))
    )
    (net (code "47") (name "Net-(IC20-G)") (class "Default")
      (node (ref "IC20") (pin "1") (pinfunction "G_1") (pintype "bidirectional"))
      (node (ref "R20") (pin "2") (pinfunction "2_2") (pintype "passive"))
      (node (ref "R46") (pin "2") (pinfunction "2_2") (pintype "passive"))
    )
    (net (code "48") (name "Net-(IC21-D)") (class "Default")
      (node (ref "IC21") (pin "4") (pinfunction "D_4") (pintype "bidirectional"))
      (node (ref "J11") (pin "1") (pinfunction "1_1") (pintype "bidirectional"))
    )
    (net (code "49") (name "Net-(IC21-G)") (class "Default")
      (node (ref "IC21") (pin "1") (pinfunction "G_1") (pintype "bidirectional"))
      (node (ref "R21") (pin "2") (pinfunction "2_2") (pintype "passive"))
      (node (ref "R47") (pin "2") (pinfunction "2_2") (pintype "passive"))
    )
    (net (code "50") (name "Net-(IC22-D)") (class "Default")
      (node (ref "IC22") (pin "4") (pinfunction "D_4") (pintype "bidirectional"))
      (node (ref "J11") (pin "2") (pinfunction "2_2") (pintype "bidirectional"))
    )
    (net (code "51") (name "Net-(IC22-G)") (class "Default")
      (node (ref "IC22") (pin "1") (pinfunction "G_1") (pintype "bidirectional"))
      (node (ref "R22") (pin "2") (pinfunction "2_2") (pintype "passive"))
      (node (ref "R48") (pin "2") (pinfunction "2_2") (pintype "passive"))
    )
    (net (code "52") (name "Net-(IC23-D)") (class "Default")
      (node (ref "IC23") (pin "4") (pinfunction "D_4") (pintype "bidirectional"))
      (node (ref "J12") (pin "1") (pinfunction "1_1") (pintype "bidirectional"))
    )
    (net (code "53") (name "Net-(IC23-G)") (class "Default")
      (node (ref "IC23") (pin "1") (pinfunction "G_1") (pintype "bidirectional"))
      (node (ref "R23") (pin "2") (pinfunction "2_2") (pintype "passive"))
      (node (ref "R49") (pin "2") (pinfunction "2_2") (pintype "passive"))
    )
    (net (code "54") (name "Net-(IC24-D)") (class "Default")
      (node (ref "IC24") (pin "4") (pinfunction "D_4") (pintype "bidirectional"))
      (node (ref "J12") (pin "2") (pinfunction "2_2") (pintype "bidirectional"))
    )
    (net (code "55") (name "Net-(IC24-G)") (class "Default")
      (node (ref "IC24") (pin "1") (pinfunction "G_1") (pintype "bidirectional"))
      (node (ref "R24") (pin "2") (pinfunction "2_2") (pintype "passive"))
      (node (ref "R50") (pin "2") (pinfunction "2_2") (pintype "passive"))
    )
    (net (code "56") (name "Net-(IC25-I)") (class "Default")
      (node (ref "C3") (pin "1") (pinfunction "1_1") (pintype "passive"))
      (node (ref "D1") (pin "C") (pinfunction "C_C") (pintype "passive"))
      (node (ref "IC25") (pin "2") (pinfunction "I_2") (pintype "bidirectional"))
    )
    (net (code "57") (name "Net-(J15-Pad2)") (class "Default")
      (node (ref "J15") (pin "2") (pinfunction "2_2") (pintype "passive"))
      (node (ref "R25") (pin "1") (pinfunction "1_1") (pintype "passive"))
    )
    (net (code "58") (name "Net-(MIDI-PadA)") (class "Default")
      (node (ref "MIDI") (pin "A") (pinfunction "A_A") (pintype "passive"))
      (node (ref "R52") (pin "1") (pinfunction "1_1") (pintype "passive"))
    )
    (net (code "59") (name "Net-(ON-PadA)") (class "Default")
      (node (ref "ON") (pin "A") (pinfunction "A_A") (pintype "passive"))
      (node (ref "R51") (pin "1") (pinfunction "1_1") (pintype "passive"))
    )
    (net (code "60") (name "Net-(U$1-D0)") (class "Default")
      (node (ref "R53") (pin "1") (pinfunction "1_1") (pintype "passive"))
      (node (ref "U$1") (pin "JP1.3") (pinfunction "D0_JP1.3") (pintype "bidirectional"))
      (node (ref "U1") (pin "13") (pinfunction "G_13") (pintype "input"))
    )
    (net (code "61") (name "Net-(U$1-D1)") (class "Default")
      (node (ref "R52") (pin "2") (pinfunction "2_2") (pintype "passive"))
      (node (ref "U$1") (pin "JP2.3") (pinfunction "D1_JP2.3") (pintype "bidirectional"))
    )
    (net (code "62") (name "Net-(U$1-D5)") (class "Default")
      (node (ref "U$1") (pin "JP1.4") (pinfunction "D5_JP1.4") (pintype "bidirectional"))
      (node (ref "U1") (pin "11") (pinfunction "SCK_11") (pintype "input"))
      (node (ref "U2") (pin "11") (pinfunction "SCK_11") (pintype "input"))
      (node (ref "U3") (pin "11") (pinfunction "SCK_11") (pintype "input"))
    )
    (net (code "63") (name "Net-(U$1-D6)") (class "Default")
      (node (ref "U$1") (pin "JP1.5") (pinfunction "D6_JP1.5") (pintype "bidirectional"))
      (node (ref "U1") (pin "14") (pinfunction "SER_14") (pintype "input"))
    )
    (net (code "64") (name "Net-(U$1-D7)") (class "Default")
      (node (ref "U$1") (pin "JP1.6") (pinfunction "D7_JP1.6") (pintype "bidirectional"))
      (node (ref "U1") (pin "12") (pinfunction "RCK_12") (pintype "input"))
      (node (ref "U2") (pin "12") (pinfunction "RCK_12") (pintype "input"))
      (node (ref "U3") (pin "12") (pinfunction "RCK_12") (pintype "input"))
    )
    (net (code "65") (name "Net-(U1-QA)") (class "Default")
      (node (ref "R1") (pin "1") (pinfunction "1_1") (pintype "passive"))
      (node (ref "U1") (pin "15") (pinfunction "QA_15") (pintype "tri_state"))
    )
    (net (code "66") (name "Net-(U1-QB)") (class "Default")
      (node (ref "R2") (pin "1") (pinfunction "1_1") (pintype "passive"))
      (node (ref "U1") (pin "1") (pinfunction "QB_1") (pintype "tri_state"))
    )
    (net (code "67") (name "Net-(U1-QC)") (class "Default")
      (node (ref "R3") (pin "1") (pinfunction "1_1") (pintype "passive"))
      (node (ref "U1") (pin "2") (pinfunction "QC_2") (pintype "tri_state"))
    )
    (net (code "68") (name "Net-(U1-QD)") (class "Default")
      (node (ref "R4") (pin "1") (pinfunction "1_1") (pintype "passive"))
      (node (ref "U1") (pin "3") (pinfunction "QD_3") (pintype "tri_state"))
    )
    (net (code "69") (name "Net-(U1-QE)") (class "Default")
      (node (ref "R5") (pin "1") (pinfunction "1_1") (pintype "passive"))
      (node (ref "U1") (pin "4") (pinfunction "QE_4") (pintype "tri_state"))
    )
    (net (code "70") (name "Net-(U1-QF)") (class "Default")
      (node (ref "R6") (pin "1") (pinfunction "1_1") (pintype "passive"))
      (node (ref "U1") (pin "5") (pinfunction "QF_5") (pintype "tri_state"))
    )
    (net (code "71") (name "Net-(U1-QG)") (class "Default")
      (node (ref "R7") (pin "1") (pinfunction "1_1") (pintype "passive"))
      (node (ref "U1") (pin "6") (pinfunction "QG_6") (pintype "tri_state"))
    )
    (net (code "72") (name "Net-(U1-QH)") (class "Default")
      (node (ref "R8") (pin "1") (pinfunction "1_1") (pintype "passive"))
      (node (ref "U1") (pin "7") (pinfunction "QH_7") (pintype "tri_state"))
    )
    (net (code "73") (name "Net-(U1-QH*)") (class "Default")
      (node (ref "U1") (pin "9") (pinfunction "QH*_9") (pintype "tri_state"))
      (node (ref "U2") (pin "14") (pinfunction "SER_14") (pintype "input"))
    )
    (net (code "74") (name "Net-(U2-QA)") (class "Default")
      (node (ref "R9") (pin "1") (pinfunction "1_1") (pintype "passive"))
      (node (ref "U2") (pin "15") (pinfunction "QA_15") (pintype "tri_state"))
    )
    (net (code "75") (name "Net-(U2-QB)") (class "Default")
      (node (ref "R10") (pin "1") (pinfunction "1_1") (pintype "passive"))
      (node (ref "U2") (pin "1") (pinfunction "QB_1") (pintype "tri_state"))
    )
    (net (code "76") (name "Net-(U2-QC)") (class "Default")
      (node (ref "R11") (pin "1") (pinfunction "1_1") (pintype "passive"))
      (node (ref "U2") (pin "2") (pinfunction "QC_2") (pintype "tri_state"))
    )
    (net (code "77") (name "Net-(U2-QD)") (class "Default")
      (node (ref "R12") (pin "1") (pinfunction "1_1") (pintype "passive"))
      (node (ref "U2") (pin "3") (pinfunction "QD_3") (pintype "tri_state"))
    )
    (net (code "78") (name "Net-(U2-QE)") (class "Default")
      (node (ref "R13") (pin "1") (pinfunction "1_1") (pintype "passive"))
      (node (ref "U2") (pin "4") (pinfunction "QE_4") (pintype "tri_state"))
    )
    (net (code "79") (name "Net-(U2-QF)") (class "Default")
      (node (ref "R14") (pin "1") (pinfunction "1_1") (pintype "passive"))
      (node (ref "U2") (pin "5") (pinfunction "QF_5") (pintype "tri_state"))
    )
    (net (code "80") (name "Net-(U2-QG)") (class "Default")
      (node (ref "R15") (pin "1") (pinfunction "1_1") (pintype "passive"))
      (node (ref "U2") (pin "6") (pinfunction "QG_6") (pintype "tri_state"))
    )
    (net (code "81") (name "Net-(U2-QH)") (class "Default")
      (node (ref "R16") (pin "1") (pinfunction "1_1") (pintype "passive"))
      (node (ref "U2") (pin "7") (pinfunction "QH_7") (pintype "tri_state"))
    )
    (net (code "82") (name "Net-(U2-QH*)") (class "Default")
      (node (ref "U2") (pin "9") (pinfunction "QH*_9") (pintype "tri_state"))
      (node (ref "U3") (pin "14") (pinfunction "SER_14") (pintype "input"))
    )
    (net (code "83") (name "Net-(U3-QA)") (class "Default")
      (node (ref "R17") (pin "1") (pinfunction "1_1") (pintype "passive"))
      (node (ref "U3") (pin "15") (pinfunction "QA_15") (pintype "tri_state"))
    )
    (net (code "84") (name "Net-(U3-QB)") (class "Default")
      (node (ref "R18") (pin "1") (pinfunction "1_1") (pintype "passive"))
      (node (ref "U3") (pin "1") (pinfunction "QB_1") (pintype "tri_state"))
    )
    (net (code "85") (name "Net-(U3-QC)") (class "Default")
      (node (ref "R19") (pin "1") (pinfunction "1_1") (pintype "passive"))
      (node (ref "U3") (pin "2") (pinfunction "QC_2") (pintype "tri_state"))
    )
    (net (code "86") (name "Net-(U3-QD)") (class "Default")
      (node (ref "R20") (pin "1") (pinfunction "1_1") (pintype "passive"))
      (node (ref "U3") (pin "3") (pinfunction "QD_3") (pintype "tri_state"))
    )
    (net (code "87") (name "Net-(U3-QE)") (class "Default")
      (node (ref "R21") (pin "1") (pinfunction "1_1") (pintype "passive"))
      (node (ref "U3") (pin "4") (pinfunction "QE_4") (pintype "tri_state"))
    )
    (net (code "88") (name "Net-(U3-QF)") (class "Default")
      (node (ref "R22") (pin "1") (pinfunction "1_1") (pintype "passive"))
      (node (ref "U3") (pin "5") (pinfunction "QF_5") (pintype "tri_state"))
    )
    (net (code "89") (name "Net-(U3-QG)") (class "Default")
      (node (ref "R23") (pin "1") (pinfunction "1_1") (pintype "passive"))
      (node (ref "U3") (pin "6") (pinfunction "QG_6") (pintype "tri_state"))
    )
    (net (code "90") (name "Net-(U3-QH)") (class "Default")
      (node (ref "R24") (pin "1") (pinfunction "1_1") (pintype "passive"))
      (node (ref "U3") (pin "7") (pinfunction "QH_7") (pintype "tri_state"))
    )
    (net (code "91") (name "unconnected-(U$1-A0-PadJP1.2)") (class "Default")
      (node (ref "U$1") (pin "JP1.2") (pinfunction "A0_JP1.2") (pintype "bidirectional"))
    )
    (net (code "92") (name "unconnected-(U$1-D2-PadJP2.4)") (class "Default")
      (node (ref "U$1") (pin "JP2.4") (pinfunction "D2_JP2.4") (pintype "bidirectional"))
    )
    (net (code "93") (name "unconnected-(U$1-D3-PadJP2.5)") (class "Default")
      (node (ref "U$1") (pin "JP2.5") (pinfunction "D3_JP2.5") (pintype "bidirectional"))
    )
    (net (code "94") (name "unconnected-(U$1-D4-PadJP2.6)") (class "Default")
      (node (ref "U$1") (pin "JP2.6") (pinfunction "D4_JP2.6") (pintype "bidirectional"))
    )
    (net (code "95") (name "unconnected-(U$1-D8-PadJP1.7)") (class "Default")
      (node (ref "U$1") (pin "JP1.7") (pinfunction "D8_JP1.7") (pintype "bidirectional"))
    )
    (net (code "96") (name "unconnected-(U$1-RST-PadJP1.1)") (class "Default")
      (node (ref "U$1") (pin "JP1.1") (pinfunction "RST_JP1.1") (pintype "bidirectional"))
    )
    (net (code "97") (name "unconnected-(U$1-TX-PadJP2.1)") (class "Default")
      (node (ref "U$1") (pin "JP2.1") (pinfunction "TX_JP2.1") (pintype "bidirectional"))
    )
    (net (code "98") (name "unconnected-(U3-QH*-Pad9)") (class "Default")
      (node (ref "U3") (pin "9") (pinfunction "QH*_9") (pintype "tri_state"))
    )
  )
)
